# NinjaPCR-131202.net
KiCad netlist of a schematic drawn in EAGLE
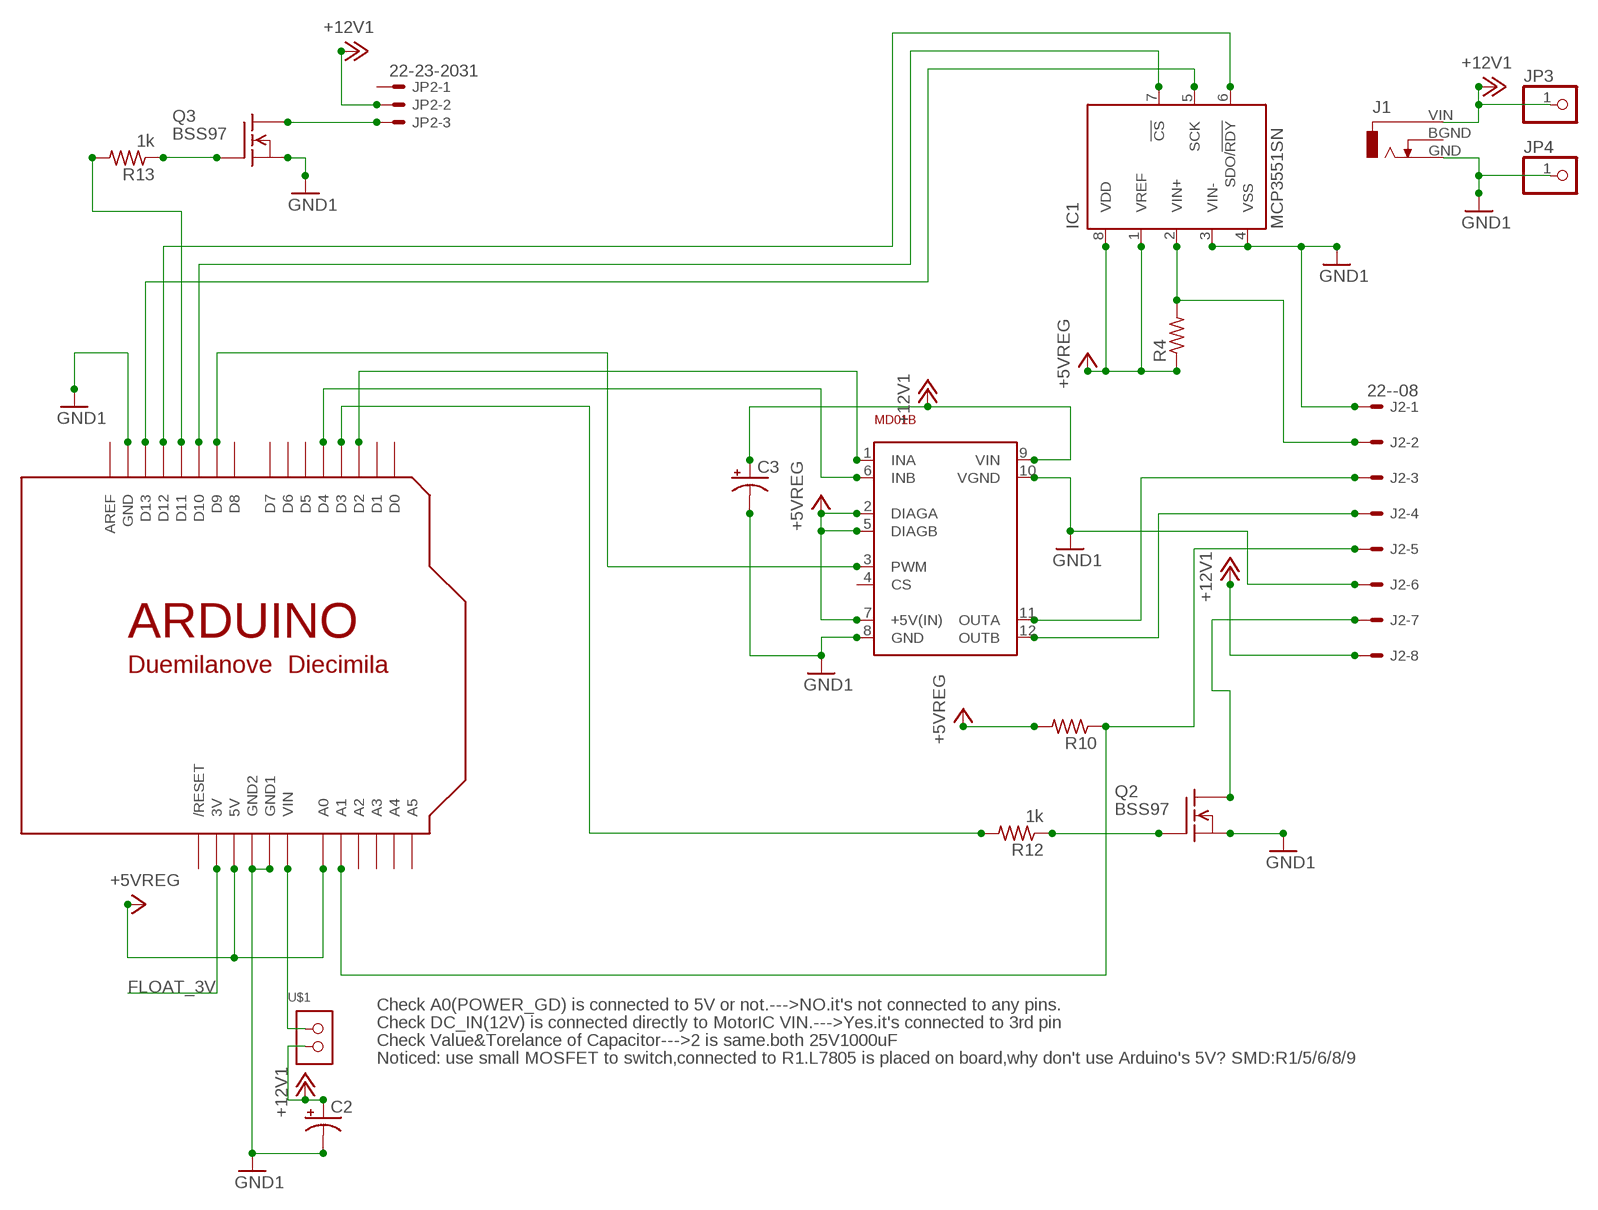
[diagram p0: schematic, sheet 1]

(export (version "E")
  (design (tool "Eeschema 10.0.6"))
  (components
    (comp (ref "C2")
      (value "CPOL-USE5-8.5")
      (footprint "eagle-import:E5-8,5")
      (libsource (lib "eagle-import") (part "CPOL-USE5-8.5"))
    )
    (comp (ref "C3")
      (value "CPOL-USE5-13")
      (footprint "eagle-import:E5-13")
      (libsource (lib "eagle-import") (part "CPOL-USE5-13"))
    )
    (comp (ref "IC1")
      (value "MCP3551SN")
      (footprint "eagle-import:SO-08")
      (fields (field (name "MPN") "MCP3551-E/SN"))
      (libsource (lib "eagle-import") (part "MCP355SN1"))
    )
    (comp (ref "J1")
      (value "DCJ0303")
      (footprint "eagle-import:DCJ0303")
      (libsource (lib "eagle-import") (part "DCJ0303"))
    )
    (comp (ref "J2")
      (value "22--08")
      (footprint "eagle-import:POLOLU-8-VERTICAL")
      (libsource (lib "eagle-import") (part "22-?-08"))
    )
    (comp (ref "JP2")
      (value "22-23-2031")
      (footprint "eagle-import:22-23-2031")
      (fields (field (name "MF") "MOLEX"))
      (libsource (lib "eagle-import") (part "22-23-2031"))
    )
    (comp (ref "JP3")
      (value "PINHD-1X1")
      (footprint "eagle-import:1X01")
      (libsource (lib "eagle-import") (part "PINHD-1X1"))
    )
    (comp (ref "JP4")
      (value "PINHD-1X1")
      (footprint "eagle-import:1X01")
      (libsource (lib "eagle-import") (part "PINHD-1X1"))
    )
    (comp (ref "MD01B")
      (value "VNH3SP30+4PINN")
      (footprint "eagle-import:VNH3SP30+4PIN_NOHOLES")
      (libsource (lib "eagle-import") (part "VNH3SP30+4PINN"))
    )
    (comp (ref "Q2")
      (value "BSS97")
      (footprint "eagle-import:TO202")
      (libsource (lib "eagle-import") (part "BSS97"))
    )
    (comp (ref "Q3")
      (value "BSS97")
      (footprint "eagle-import:TO202")
      (libsource (lib "eagle-import") (part "BSS97"))
    )
    (comp (ref "R4")
      (value "R-US_0207/10")
      (footprint "eagle-import:0207_10")
      (libsource (lib "eagle-import") (part "R-US_0207/10"))
    )
    (comp (ref "R10")
      (value "R-US_0207/10")
      (footprint "eagle-import:0207_10")
      (libsource (lib "eagle-import") (part "R-US_0207/10"))
    )
    (comp (ref "R12")
      (value "1k")
      (footprint "eagle-import:0207_10")
      (libsource (lib "eagle-import") (part "R-US_0207/10"))
    )
    (comp (ref "R13")
      (value "1k")
      (footprint "eagle-import:0207_10")
      (libsource (lib "eagle-import") (part "R-US_0207/10"))
    )
    (comp (ref "U$1")
      (value "1X02")
      (footprint "eagle-import:1X02_1.1_UNSIGNED")
      (libsource (lib "eagle-import") (part "1X02"))
    )
    (comp (ref "U$3")
      (value "ARDUINODUEMILANOVE")
      (footprint "eagle-import:ARDUINO")
      (libsource (lib "eagle-import") (part "ARDUINODUEMILANOVE"))
    )
  )
  (nets
    (net (code "1") (name "+5VREG") (class "Default")
      (node (ref "IC1") (pin "1") (pinfunction "VREF_1") (pintype "input"))
      (node (ref "IC1") (pin "8") (pinfunction "VDD_8") (pintype "power_in"))
      (node (ref "MD01B") (pin "2") (pinfunction "DIAGA_2") (pintype "passive"))
      (node (ref "MD01B") (pin "5") (pinfunction "DIAGB_5") (pintype "passive"))
      (node (ref "MD01B") (pin "7") (pinfunction "+5V(IN)_7") (pintype "power_in"))
      (node (ref "R10") (pin "2") (pinfunction "2_2") (pintype "passive"))
      (node (ref "R4") (pin "1") (pinfunction "1_1") (pintype "passive"))
      (node (ref "U$3") (pin "5V") (pinfunction "5V_5V") (pintype "power_in"))
      (node (ref "U$3") (pin "A0") (pinfunction "A0_A0") (pintype "bidirectional"))
    )
    (net (code "2") (name "+12V1") (class "Default")
      (node (ref "C2") (pin "+") (pinfunction "+_+") (pintype "passive"))
      (node (ref "C3") (pin "+") (pinfunction "+_+") (pintype "passive"))
      (node (ref "J1") (pin "VIN") (pinfunction "VIN_VIN") (pintype "passive"))
      (node (ref "J2") (pin "8") (pinfunction "S_8") (pintype "passive"))
      (node (ref "JP2") (pin "2") (pinfunction "S_2") (pintype "passive"))
      (node (ref "JP3") (pin "1") (pinfunction "1_1") (pintype "passive"))
      (node (ref "MD01B") (pin "9") (pinfunction "VIN_9") (pintype "power_in"))
      (node (ref "U$1") (pin "2") (pinfunction "2_2") (pintype "passive"))
    )
    (net (code "3") (name "/FLOAT_3V") (class "Default")
      (node (ref "U$3") (pin "3V") (pinfunction "3V_3V") (pintype "power_in"))
    )
    (net (code "4") (name "GND1") (class "Default")
      (node (ref "C2") (pin "-") (pinfunction "-_-") (pintype "passive"))
      (node (ref "C3") (pin "-") (pinfunction "-_-") (pintype "passive"))
      (node (ref "IC1") (pin "3") (pinfunction "VIN-_3") (pintype "input"))
      (node (ref "IC1") (pin "4") (pinfunction "VSS_4") (pintype "power_in"))
      (node (ref "J1") (pin "GND") (pinfunction "GND_GND") (pintype "passive"))
      (node (ref "J2") (pin "1") (pinfunction "S_1") (pintype "passive"))
      (node (ref "J2") (pin "6") (pinfunction "S_6") (pintype "passive"))
      (node (ref "JP4") (pin "1") (pinfunction "1_1") (pintype "passive"))
      (node (ref "MD01B") (pin "10") (pinfunction "VGND_10") (pintype "power_in"))
      (node (ref "MD01B") (pin "8") (pinfunction "GND_8") (pintype "power_in"))
      (node (ref "Q2") (pin "1") (pinfunction "S_1") (pintype "passive"))
      (node (ref "Q3") (pin "1") (pinfunction "S_1") (pintype "passive"))
      (node (ref "U$3") (pin "GND") (pinfunction "GND_GND") (pintype "power_in"))
      (node (ref "U$3") (pin "GND1") (pinfunction "GND1_GND1") (pintype "power_in"))
      (node (ref "U$3") (pin "GND2") (pinfunction "GND2_GND2") (pintype "power_in"))
    )
    (net (code "5") (name "Net-(IC1-SCK)") (class "Default")
      (node (ref "IC1") (pin "5") (pinfunction "SCK_5") (pintype "input"))
      (node (ref "U$3") (pin "D13") (pinfunction "D13_D13") (pintype "bidirectional"))
    )
    (net (code "6") (name "Net-(IC1-SDO{slash}~{RDY})") (class "Default")
      (node (ref "IC1") (pin "6") (pinfunction "SDO/~{RDY}_6") (pintype "output"))
      (node (ref "U$3") (pin "D12") (pinfunction "D12_D12") (pintype "bidirectional"))
    )
    (net (code "7") (name "Net-(IC1-VIN+)") (class "Default")
      (node (ref "IC1") (pin "2") (pinfunction "VIN+_2") (pintype "input"))
      (node (ref "J2") (pin "2") (pinfunction "S_2") (pintype "passive"))
      (node (ref "R4") (pin "2") (pinfunction "2_2") (pintype "passive"))
    )
    (net (code "8") (name "Net-(IC1-~{CS})") (class "Default")
      (node (ref "IC1") (pin "7") (pinfunction "~{CS}_7") (pintype "input"))
      (node (ref "U$3") (pin "D10") (pinfunction "D10_D10") (pintype "bidirectional"))
    )
    (net (code "9") (name "Net-(J2C-S)") (class "Default")
      (node (ref "J2") (pin "3") (pinfunction "S_3") (pintype "passive"))
      (node (ref "MD01B") (pin "11") (pinfunction "OUTA_11") (pintype "passive"))
    )
    (net (code "10") (name "Net-(J2D-S)") (class "Default")
      (node (ref "J2") (pin "4") (pinfunction "S_4") (pintype "passive"))
      (node (ref "MD01B") (pin "12") (pinfunction "OUTB_12") (pintype "passive"))
    )
    (net (code "11") (name "Net-(J2E-S)") (class "Default")
      (node (ref "J2") (pin "5") (pinfunction "S_5") (pintype "passive"))
      (node (ref "R10") (pin "1") (pinfunction "1_1") (pintype "passive"))
      (node (ref "U$3") (pin "A1") (pinfunction "A1_A1") (pintype "bidirectional"))
    )
    (net (code "12") (name "Net-(J2G-S)") (class "Default")
      (node (ref "J2") (pin "7") (pinfunction "S_7") (pintype "passive"))
      (node (ref "Q2") (pin "2") (pinfunction "D_2") (pintype "passive"))
    )
    (net (code "13") (name "Net-(JP2C-S)") (class "Default")
      (node (ref "JP2") (pin "3") (pinfunction "S_3") (pintype "passive"))
      (node (ref "Q3") (pin "2") (pinfunction "D_2") (pintype "passive"))
    )
    (net (code "14") (name "Net-(MD01B-INA)") (class "Default")
      (node (ref "MD01B") (pin "1") (pinfunction "INA_1") (pintype "passive"))
      (node (ref "U$3") (pin "D2") (pinfunction "D2_D2") (pintype "bidirectional"))
    )
    (net (code "15") (name "Net-(MD01B-INB)") (class "Default")
      (node (ref "MD01B") (pin "6") (pinfunction "INB_6") (pintype "passive"))
      (node (ref "U$3") (pin "D4") (pinfunction "D4_D4") (pintype "bidirectional"))
    )
    (net (code "16") (name "Net-(MD01B-PWM)") (class "Default")
      (node (ref "MD01B") (pin "3") (pinfunction "PWM_3") (pintype "passive"))
      (node (ref "U$3") (pin "D9") (pinfunction "D9_D9") (pintype "bidirectional"))
    )
    (net (code "17") (name "Net-(Q2-G)") (class "Default")
      (node (ref "Q2") (pin "3") (pinfunction "G_3") (pintype "passive"))
      (node (ref "R12") (pin "1") (pinfunction "1_1") (pintype "passive"))
    )
    (net (code "18") (name "Net-(Q3-G)") (class "Default")
      (node (ref "Q3") (pin "3") (pinfunction "G_3") (pintype "passive"))
      (node (ref "R13") (pin "1") (pinfunction "1_1") (pintype "passive"))
    )
    (net (code "19") (name "Net-(R12-Pad2)") (class "Default")
      (node (ref "R12") (pin "2") (pinfunction "2_2") (pintype "passive"))
      (node (ref "U$3") (pin "D3") (pinfunction "D3_D3") (pintype "bidirectional"))
    )
    (net (code "20") (name "Net-(R13-Pad2)") (class "Default")
      (node (ref "R13") (pin "2") (pinfunction "2_2") (pintype "passive"))
      (node (ref "U$3") (pin "D11") (pinfunction "D11_D11") (pintype "bidirectional"))
    )
    (net (code "21") (name "Net-(U$1-Pad1)") (class "Default")
      (node (ref "U$1") (pin "1") (pinfunction "1_1") (pintype "passive"))
      (node (ref "U$3") (pin "VIN") (pinfunction "VIN_VIN") (pintype "power_in"))
    )
    (net (code "22") (name "unconnected-(J1-PadBGND)") (class "Default")
      (node (ref "J1") (pin "BGND") (pinfunction "BGND_BGND") (pintype "passive"))
    )
    (net (code "23") (name "unconnected-(JP2A-S-Pad1)") (class "Default")
      (node (ref "JP2") (pin "1") (pinfunction "S_1") (pintype "passive"))
    )
    (net (code "24") (name "unconnected-(MD01B-CS-Pad4)") (class "Default")
      (node (ref "MD01B") (pin "4") (pinfunction "CS_4") (pintype "passive"))
    )
    (net (code "25") (name "unconnected-(U$3-PadA2)") (class "Default")
      (node (ref "U$3") (pin "A2") (pinfunction "A2_A2") (pintype "bidirectional"))
    )
    (net (code "26") (name "unconnected-(U$3-PadA3)") (class "Default")
      (node (ref "U$3") (pin "A3") (pinfunction "A3_A3") (pintype "bidirectional"))
    )
    (net (code "27") (name "unconnected-(U$3-PadA4)") (class "Default")
      (node (ref "U$3") (pin "A4") (pinfunction "A4_A4") (pintype "bidirectional"))
    )
    (net (code "28") (name "unconnected-(U$3-PadA5)") (class "Default")
      (node (ref "U$3") (pin "A5") (pinfunction "A5_A5") (pintype "bidirectional"))
    )
    (net (code "29") (name "unconnected-(U$3-PadAREF)") (class "Default")
      (node (ref "U$3") (pin "AREF") (pinfunction "AREF_AREF") (pintype "bidirectional"))
    )
    (net (code "30") (name "unconnected-(U$3-PadD0)") (class "Default")
      (node (ref "U$3") (pin "D0") (pinfunction "D0_D0") (pintype "bidirectional"))
    )
    (net (code "31") (name "unconnected-(U$3-PadD1)") (class "Default")
      (node (ref "U$3") (pin "D1") (pinfunction "D1_D1") (pintype "bidirectional"))
    )
    (net (code "32") (name "unconnected-(U$3-PadD5)") (class "Default")
      (node (ref "U$3") (pin "D5") (pinfunction "D5_D5") (pintype "bidirectional"))
    )
    (net (code "33") (name "unconnected-(U$3-PadD6)") (class "Default")
      (node (ref "U$3") (pin "D6") (pinfunction "D6_D6") (pintype "bidirectional"))
    )
    (net (code "34") (name "unconnected-(U$3-PadD7)") (class "Default")
      (node (ref "U$3") (pin "D7") (pinfunction "D7_D7") (pintype "bidirectional"))
    )
    (net (code "35") (name "unconnected-(U$3-PadD8)") (class "Default")
      (node (ref "U$3") (pin "D8") (pinfunction "D8_D8") (pintype "bidirectional"))
    )
    (net (code "36") (name "unconnected-(U$3-{slash}RESET-PadRESET)") (class "Default")
      (node (ref "U$3") (pin "RESET") (pinfunction "/RESET_RESET") (pintype "bidirectional"))
    )
  )
)
